# PROC054D_40MHZ_Clock.net
KiCad netlist of a schematic drawn in Altium Designer
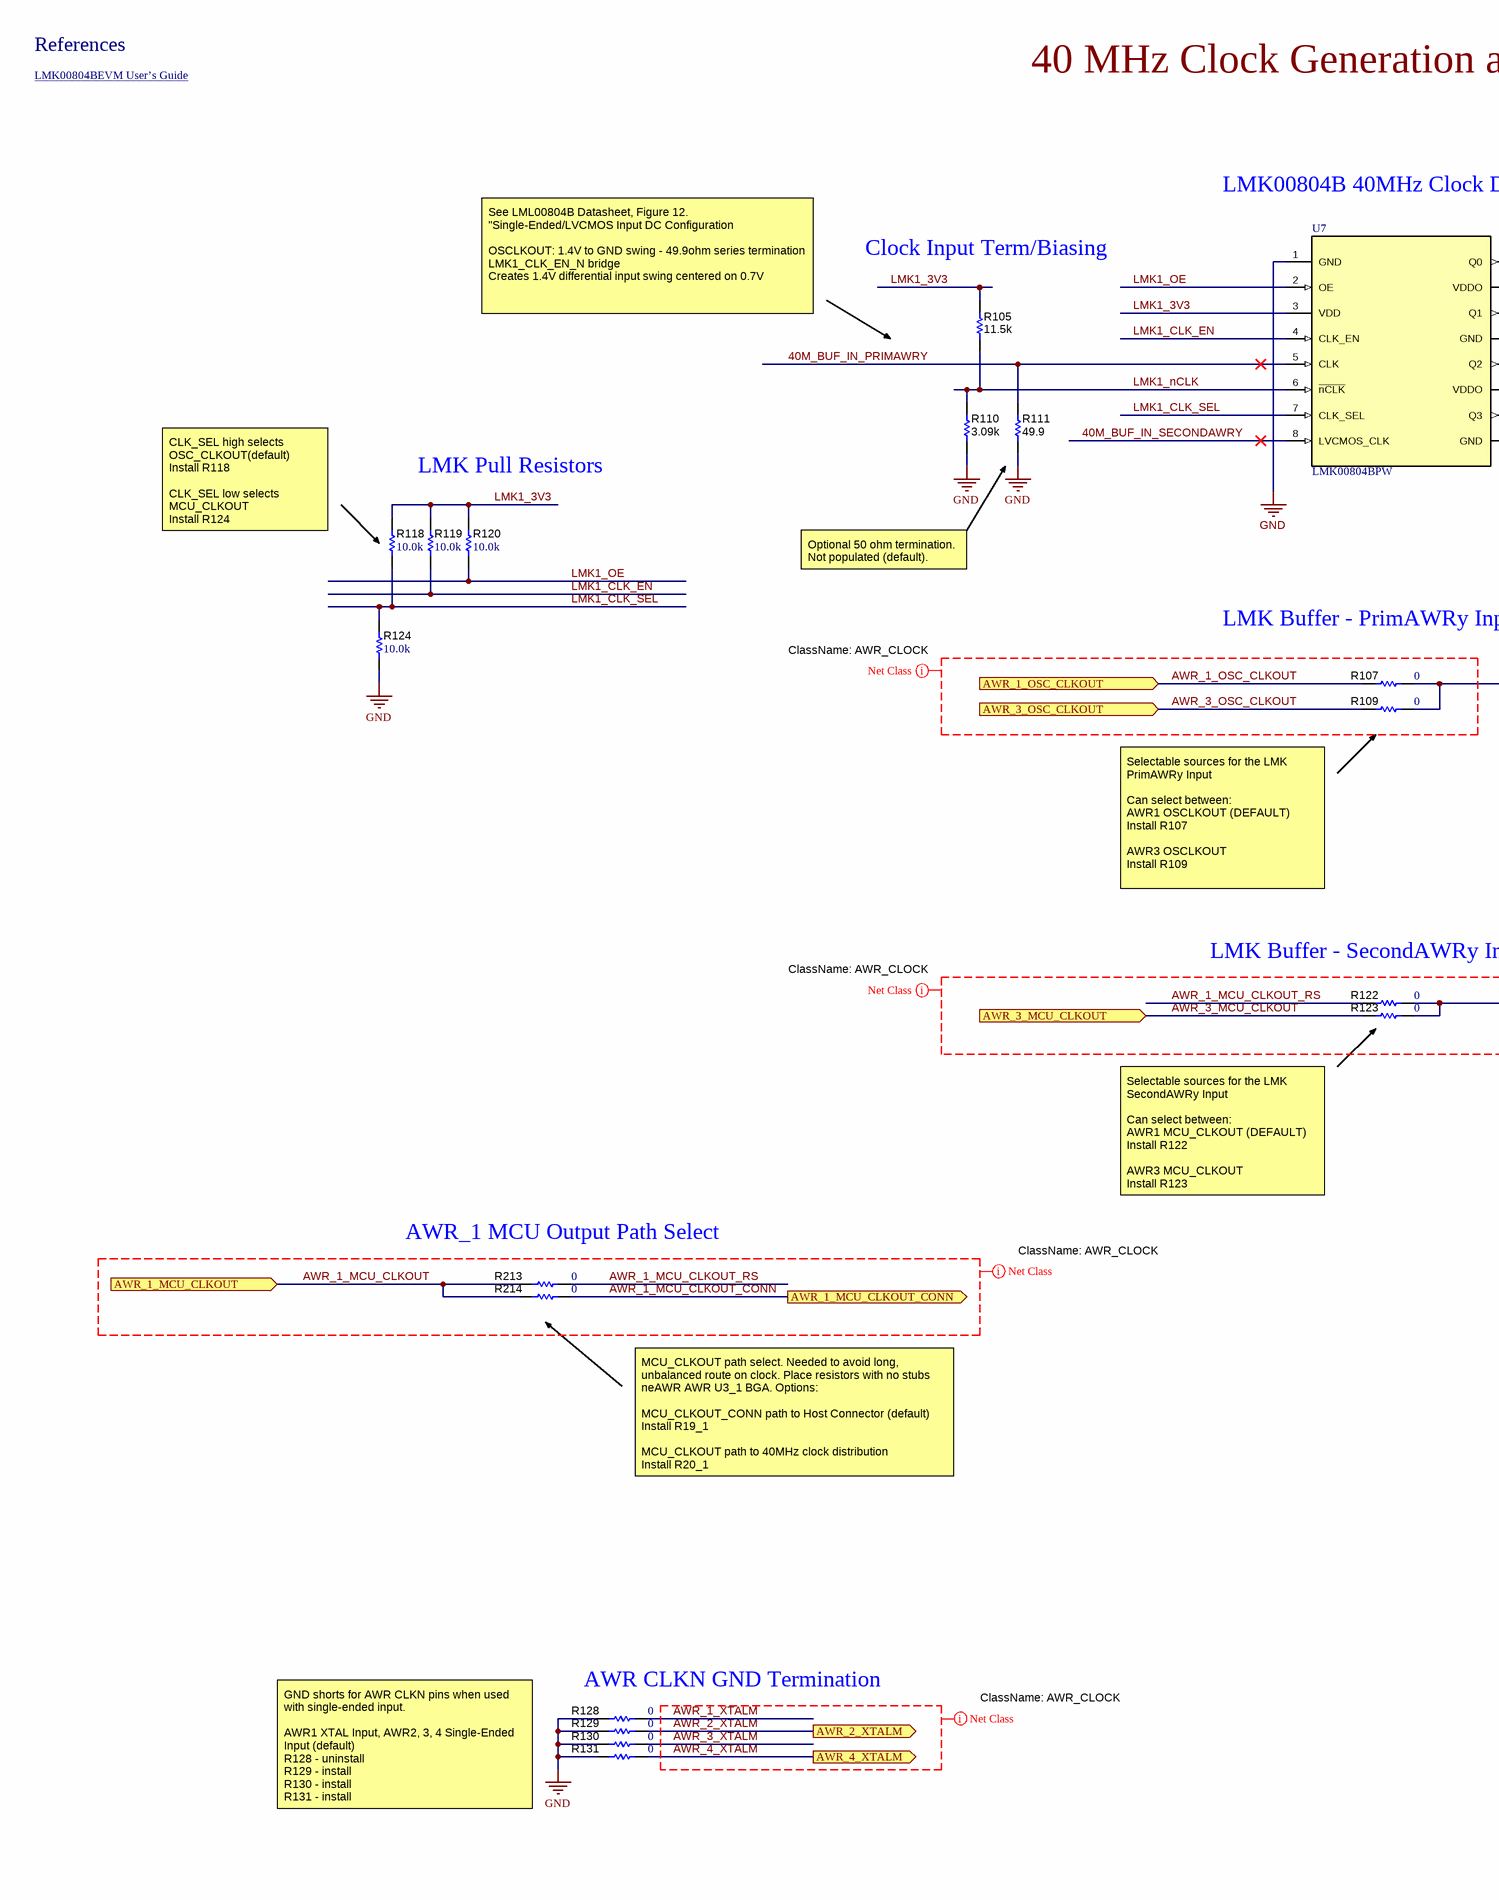
[diagram p0: PROC054D_40MHZ_Clock.SchDoc, left]
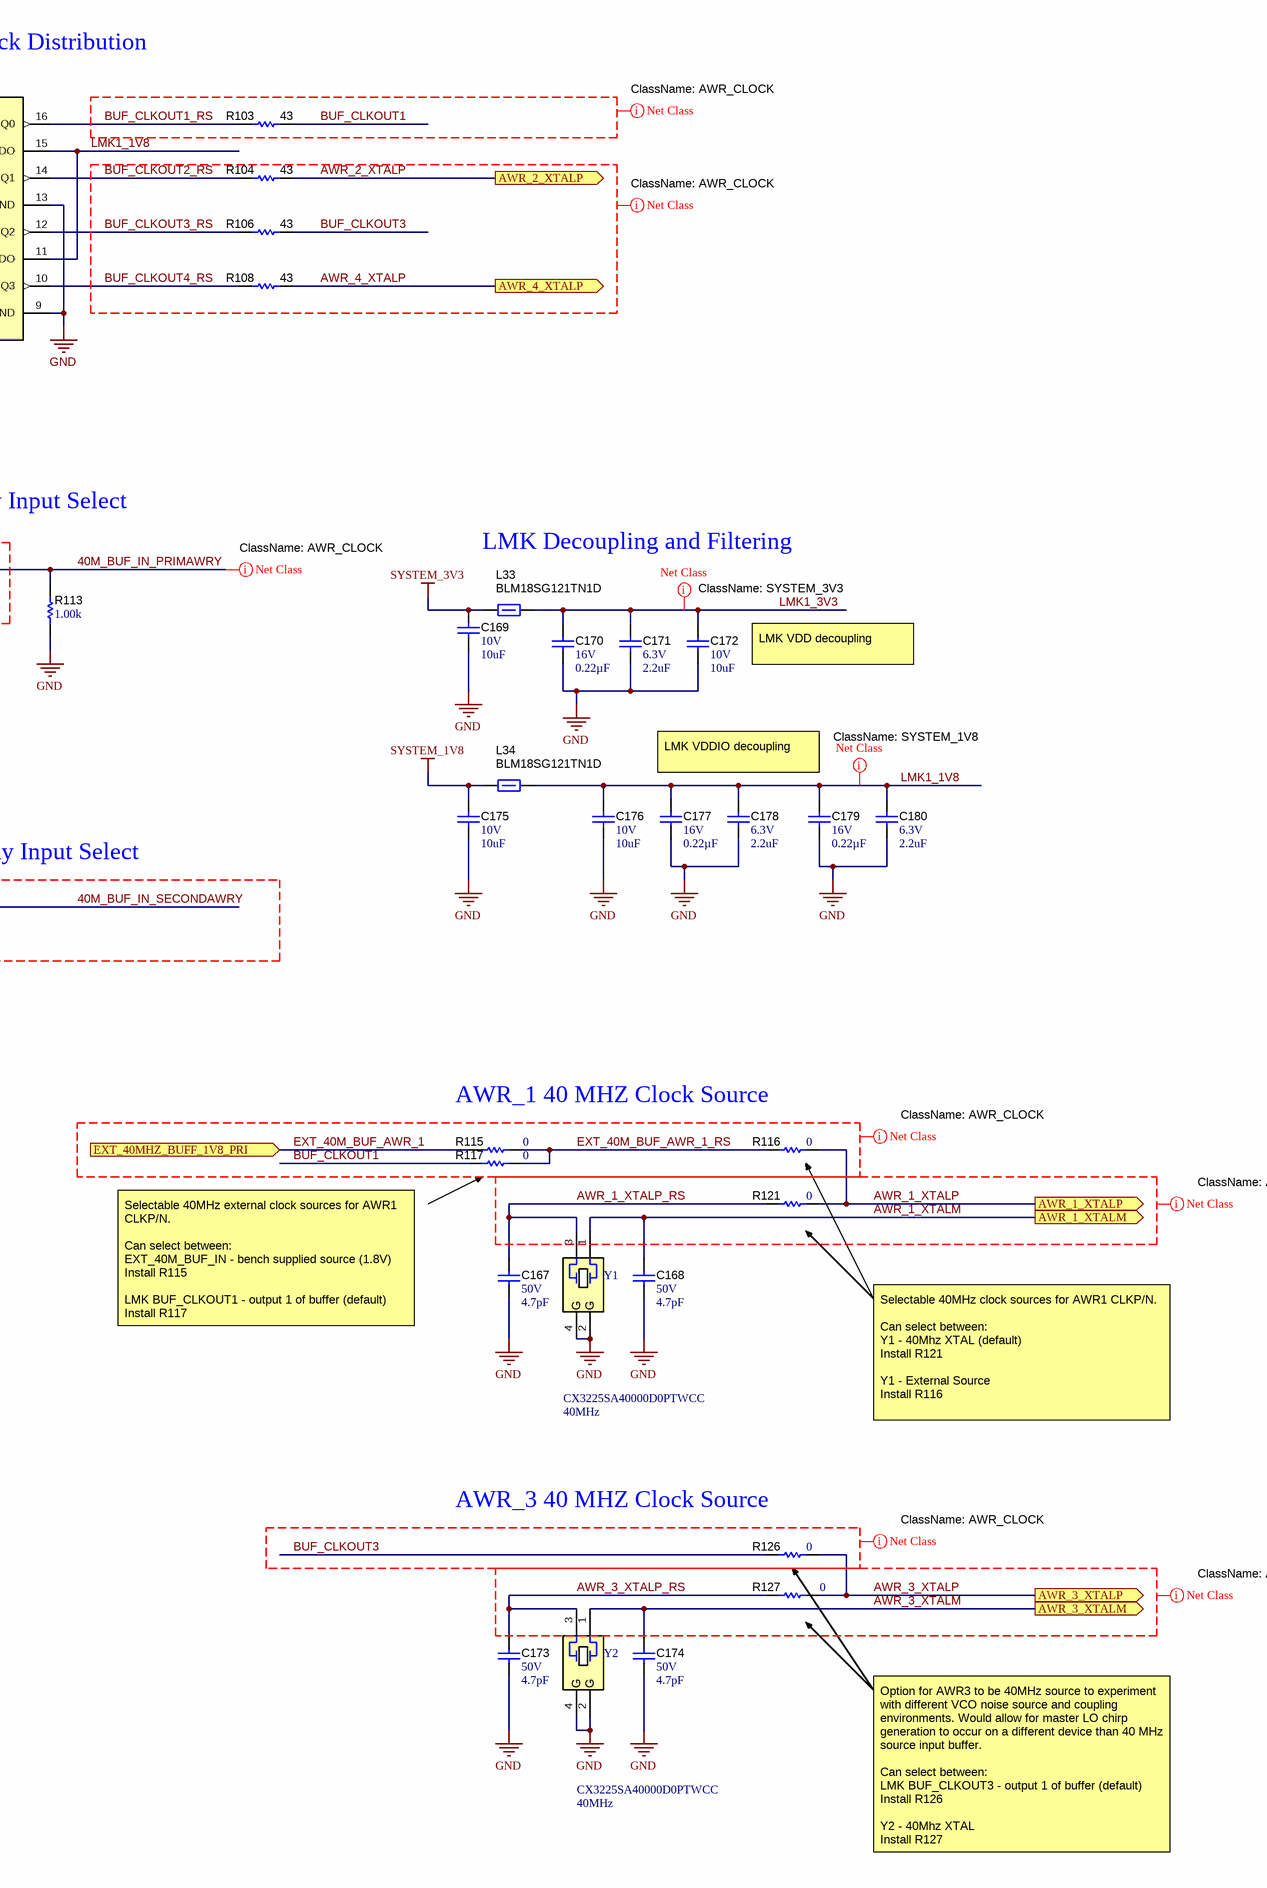
[diagram p1: PROC054D_40MHZ_Clock.SchDoc, right]

(export (version "E")
  (design (tool "Eeschema 10.0.6"))
  (components
    (comp (ref "C167")
      (value "GJM1555C1H4R7BB01D")
      (footprint "0402")
      (description "CAP, CERM, 4.7 pF, 50 V, +/- 2%, C0G/NP0, 0402")
      (fields
        (field (name "MANUFACTURER") "MuRata")
        (field (name "VDC_V") "50V")
        (field (name "VALUEDISPLAYED") "4.7pF")
        (field (name "PUBLISHER") "Texas Instruments")
      )
      (libsource (lib "Altium Vault - TI") (part "Capacitor"))
    )
    (comp (ref "C168")
      (value "GJM1555C1H4R7BB01D")
      (footprint "0402")
      (description "CAP, CERM, 4.7 pF, 50 V, +/- 2%, C0G/NP0, 0402")
      (fields
        (field (name "MANUFACTURER") "MuRata")
        (field (name "VDC_V") "50V")
        (field (name "VALUEDISPLAYED") "4.7pF")
        (field (name "PUBLISHER") "Texas Instruments")
      )
      (libsource (lib "Altium Vault - TI") (part "Capacitor"))
    )
    (comp (ref "C169")
      (value "GCM21BR71A106KE22L")
      (footprint "0805_HV")
      (description "CAP, CERM, 10 uF, 10 V, +/- 10%, X7R, 0805")
      (fields
        (field (name "MANUFACTURER") "MuRata")
        (field (name "VDC_V") "10V")
        (field (name "VALUEDISPLAYED") "10uF")
        (field (name "PUBLISHER") "Texas Instruments")
      )
      (libsource (lib "Altium Vault - TI") (part "CMP-0008017-2"))
    )
    (comp (ref "C170")
      (value "GCM155R71C224KE02D")
      (footprint "0402")
      (description "CAP, CERM, 0.22 µF, 16 V,+/- 10%, X7R, AEC-Q200 Grade 1, 0402")
      (fields
        (field (name "MANUFACTURER") "MuRata")
        (field (name "VDC_V") "16V")
        (field (name "VALUEDISPLAYED") "0.22µF")
      )
      (libsource (lib "Altium Vault - TI") (part "CMP-0078265-1"))
    )
    (comp (ref "C171")
      (value "GCM188R70J225KE22D")
      (footprint "0603")
      (description "CAP, CERM, 2.2 uF, 6.3 V, +/- 10%, X7R, AEC-Q200 Grade 1, 0603")
      (fields
        (field (name "MANUFACTURER") "MuRata")
        (field (name "VDC_V") "6.3V")
        (field (name "VALUEDISPLAYED") "2.2uF")
        (field (name "PUBLISHER") "Texas Instruments")
      )
      (libsource (lib "Altium Vault - TI") (part "Capacitor"))
    )
    (comp (ref "C172")
      (value "GCM21BR71A106KE22L")
      (footprint "0805_HV")
      (description "CAP, CERM, 10 uF, 10 V, +/- 10%, X7R, 0805")
      (fields
        (field (name "MANUFACTURER") "MuRata")
        (field (name "VDC_V") "10V")
        (field (name "VALUEDISPLAYED") "10uF")
        (field (name "PUBLISHER") "Texas Instruments")
      )
      (libsource (lib "Altium Vault - TI") (part "CMP-0008017-2"))
    )
    (comp (ref "C173")
      (value "GJM1555C1H4R7BB01D")
      (footprint "0402")
      (description "CAP, CERM, 4.7 pF, 50 V, +/- 2%, C0G/NP0, 0402")
      (fields
        (field (name "MANUFACTURER") "MuRata")
        (field (name "VDC_V") "50V")
        (field (name "VALUEDISPLAYED") "4.7pF")
        (field (name "PUBLISHER") "Texas Instruments")
      )
      (libsource (lib "Altium Vault - TI") (part "Capacitor"))
    )
    (comp (ref "C174")
      (value "GJM1555C1H4R7BB01D")
      (footprint "0402")
      (description "CAP, CERM, 4.7 pF, 50 V, +/- 2%, C0G/NP0, 0402")
      (fields
        (field (name "MANUFACTURER") "MuRata")
        (field (name "VDC_V") "50V")
        (field (name "VALUEDISPLAYED") "4.7pF")
        (field (name "PUBLISHER") "Texas Instruments")
      )
      (libsource (lib "Altium Vault - TI") (part "Capacitor"))
    )
    (comp (ref "C175")
      (value "GCM21BR71A106KE22L")
      (footprint "0805_HV")
      (description "CAP, CERM, 10 uF, 10 V, +/- 10%, X7R, 0805")
      (fields
        (field (name "MANUFACTURER") "MuRata")
        (field (name "VDC_V") "10V")
        (field (name "VALUEDISPLAYED") "10uF")
        (field (name "PUBLISHER") "Texas Instruments")
      )
      (libsource (lib "Altium Vault - TI") (part "CMP-0008017-2"))
    )
    (comp (ref "C176")
      (value "GCM21BR71A106KE22L")
      (footprint "0805_HV")
      (description "CAP, CERM, 10 uF, 10 V, +/- 10%, X7R, 0805")
      (fields
        (field (name "MANUFACTURER") "MuRata")
        (field (name "VDC_V") "10V")
        (field (name "VALUEDISPLAYED") "10uF")
        (field (name "PUBLISHER") "Texas Instruments")
      )
      (libsource (lib "Altium Vault - TI") (part "CMP-0008017-2"))
    )
    (comp (ref "C177")
      (value "GCM155R71C224KE02D")
      (footprint "0402")
      (description "CAP, CERM, 0.22 µF, 16 V,+/- 10%, X7R, AEC-Q200 Grade 1, 0402")
      (fields
        (field (name "MANUFACTURER") "MuRata")
        (field (name "VDC_V") "16V")
        (field (name "VALUEDISPLAYED") "0.22µF")
      )
      (libsource (lib "Altium Vault - TI") (part "CMP-0078265-1"))
    )
    (comp (ref "C178")
      (value "GCM188R70J225KE22D")
      (footprint "0603")
      (description "CAP, CERM, 2.2 uF, 6.3 V, +/- 10%, X7R, AEC-Q200 Grade 1, 0603")
      (fields
        (field (name "MANUFACTURER") "MuRata")
        (field (name "VDC_V") "6.3V")
        (field (name "VALUEDISPLAYED") "2.2uF")
        (field (name "PUBLISHER") "Texas Instruments")
      )
      (libsource (lib "Altium Vault - TI") (part "Capacitor"))
    )
    (comp (ref "C179")
      (value "GCM155R71C224KE02D")
      (footprint "0402")
      (description "CAP, CERM, 0.22 µF, 16 V,+/- 10%, X7R, AEC-Q200 Grade 1, 0402")
      (fields
        (field (name "MANUFACTURER") "MuRata")
        (field (name "VDC_V") "16V")
        (field (name "VALUEDISPLAYED") "0.22µF")
      )
      (libsource (lib "Altium Vault - TI") (part "CMP-0078265-1"))
    )
    (comp (ref "C180")
      (value "GCM188R70J225KE22D")
      (footprint "0603")
      (description "CAP, CERM, 2.2 uF, 6.3 V, +/- 10%, X7R, AEC-Q200 Grade 1, 0603")
      (fields
        (field (name "MANUFACTURER") "MuRata")
        (field (name "VDC_V") "6.3V")
        (field (name "VALUEDISPLAYED") "2.2uF")
        (field (name "PUBLISHER") "Texas Instruments")
      )
      (libsource (lib "Altium Vault - TI") (part "Capacitor"))
    )
    (comp (ref "L33")
      (value "BLM18SG121TN1D")
      (footprint "0603")
      (description "Ferrite Bead, 120 ohm @ 100 MHz, 3 A, 0603")
      (fields (field (name "MANUFACTURER") "MuRata") (field (name "PUBLISHER") "Texas Instruments"))
      (libsource (lib "Altium Vault - TI") (part "CMP-0003352-2"))
    )
    (comp (ref "L34")
      (value "BLM18SG121TN1D")
      (footprint "0603")
      (description "Ferrite Bead, 120 ohm @ 100 MHz, 3 A, 0603")
      (fields (field (name "MANUFACTURER") "MuRata") (field (name "PUBLISHER") "Texas Instruments"))
      (libsource (lib "Altium Vault - TI") (part "CMP-0003352-2"))
    )
    (comp (ref "R103")
      (value "CRCW040243R0JNED")
      (footprint "0402")
      (description "RES, 43, 5%, 0.063 W, AEC-Q200 Grade 0, 0402")
      (fields (field (name "MANUFACTURER") "Vishay-Dale") (field (name "VALUEDISPLAYED") "43"))
      (libsource (lib "Altium Vault - TI") (part "Resistor"))
    )
    (comp (ref "R104")
      (value "CRCW040243R0JNED")
      (footprint "0402")
      (description "RES, 43, 5%, 0.063 W, AEC-Q200 Grade 0, 0402")
      (fields (field (name "MANUFACTURER") "Vishay-Dale") (field (name "VALUEDISPLAYED") "43"))
      (libsource (lib "Altium Vault - TI") (part "Resistor"))
    )
    (comp (ref "R105")
      (value "ERJ-2RKF1152X")
      (footprint "0402")
      (description "RES, 11.5 k, 1%, 0.1 W, AEC-Q200 Grade 0, 0402")
      (fields (field (name "MANUFACTURER") "Panasonic") (field (name "VALUEDISPLAYED") "11.5k"))
      (libsource (lib "Altium Vault - TI") (part "Resistor"))
    )
    (comp (ref "R106")
      (value "CRCW040243R0JNED")
      (footprint "0402")
      (description "RES, 43, 5%, 0.063 W, AEC-Q200 Grade 0, 0402")
      (fields (field (name "MANUFACTURER") "Vishay-Dale") (field (name "VALUEDISPLAYED") "43"))
      (libsource (lib "Altium Vault - TI") (part "Resistor"))
    )
    (comp (ref "R107")
      (value "ERJ-2GE0R00X")
      (footprint "0402")
      (description "RES, 0, 5%, 0.1 W, AEC-Q200 Grade 0, 0402")
      (fields (field (name "MANUFACTURER") "Panasonic") (field (name "VALUEDISPLAYED") "0"))
      (libsource (lib "Altium Vault - TI") (part "Resistor"))
    )
    (comp (ref "R108")
      (value "CRCW040243R0JNED")
      (footprint "0402")
      (description "RES, 43, 5%, 0.063 W, AEC-Q200 Grade 0, 0402")
      (fields (field (name "MANUFACTURER") "Vishay-Dale") (field (name "VALUEDISPLAYED") "43"))
      (libsource (lib "Altium Vault - TI") (part "Resistor"))
    )
    (comp (ref "R109")
      (value "ERJ-2GE0R00X")
      (footprint "0402")
      (description "RES, 0, 5%, 0.1 W, AEC-Q200 Grade 0, 0402")
      (fields (field (name "MANUFACTURER") "Panasonic") (field (name "VALUEDISPLAYED") "0"))
      (libsource (lib "Altium Vault - TI") (part "Resistor"))
    )
    (comp (ref "R110")
      (value "ERJ-2RKF3091X")
      (footprint "0402")
      (description "RES, 3.09 k, 1%, 0.1 W, AEC-Q200 Grade 0, 0402")
      (fields (field (name "MANUFACTURER") "Panasonic") (field (name "VALUEDISPLAYED") "3.09k"))
      (libsource (lib "Altium Vault - TI") (part "Resistor"))
    )
    (comp (ref "R111")
      (value "ERJ-2RKF49R9X")
      (footprint "0402")
      (description "RES, 49.9, 1%, 0.1 W, AEC-Q200 Grade 0, 0402")
      (fields
        (field (name "MANUFACTURER") "Panasonic")
        (field (name "VALUEDISPLAYED") "49.9")
        (field (name "PUBLISHER") "Texas Instruments")
      )
      (libsource (lib "Altium Vault - TI") (part "Resistor"))
    )
    (comp (ref "R113")
      (value "CRCW04021K00FKED")
      (footprint "0402")
      (description "RES, 1.00 k, 1%, 0.063 W, AEC-Q200 Grade 0, 0402")
      (fields (field (name "MANUFACTURER") "Vishay-Dale") (field (name "VALUEDISPLAYED") "1.00k"))
      (libsource (lib "Altium Vault - TI") (part "Resistor"))
    )
    (comp (ref "R115")
      (value "ERJ-2GE0R00X")
      (footprint "0402")
      (description "RES, 0, 5%, 0.1 W, AEC-Q200 Grade 0, 0402")
      (fields (field (name "MANUFACTURER") "Panasonic") (field (name "VALUEDISPLAYED") "0"))
      (libsource (lib "Altium Vault - TI") (part "CMP-0026992-3"))
    )
    (comp (ref "R116")
      (value "ERJ-2GE0R00X")
      (footprint "0402")
      (description "RES, 0, 5%, 0.1 W, AEC-Q200 Grade 0, 0402")
      (fields (field (name "MANUFACTURER") "Panasonic") (field (name "VALUEDISPLAYED") "0"))
      (libsource (lib "Altium Vault - TI") (part "CMP-0026992-3"))
    )
    (comp (ref "R117")
      (value "ERJ-2GE0R00X")
      (footprint "0402")
      (description "RES, 0, 5%, 0.1 W, AEC-Q200 Grade 0, 0402")
      (fields (field (name "MANUFACTURER") "Panasonic") (field (name "VALUEDISPLAYED") "0"))
      (libsource (lib "Altium Vault - TI") (part "Resistor"))
    )
    (comp (ref "R118")
      (value "CRCW040210K0FKED")
      (footprint "0402")
      (description "RES, 10.0 k, 1%, 0.063 W, AEC-Q200 Grade 0, 0402")
      (fields (field (name "MANUFACTURER") "Vishay-Dale") (field (name "VALUEDISPLAYED") "10.0k"))
      (libsource (lib "Altium Vault - TI") (part "Resistor"))
    )
    (comp (ref "R119")
      (value "CRCW040210K0FKED")
      (footprint "0402")
      (description "RES, 10.0 k, 1%, 0.063 W, AEC-Q200 Grade 0, 0402")
      (fields (field (name "MANUFACTURER") "Vishay-Dale") (field (name "VALUEDISPLAYED") "10.0k"))
      (libsource (lib "Altium Vault - TI") (part "Resistor"))
    )
    (comp (ref "R120")
      (value "CRCW040210K0FKED")
      (footprint "0402")
      (description "RES, 10.0 k, 1%, 0.063 W, AEC-Q200 Grade 0, 0402")
      (fields (field (name "MANUFACTURER") "Vishay-Dale") (field (name "VALUEDISPLAYED") "10.0k"))
      (libsource (lib "Altium Vault - TI") (part "Resistor"))
    )
    (comp (ref "R121")
      (value "ERJ-2GE0R00X")
      (footprint "0402")
      (description "RES, 0, 5%, 0.1 W, AEC-Q200 Grade 0, 0402")
      (fields (field (name "MANUFACTURER") "Panasonic") (field (name "VALUEDISPLAYED") "0"))
      (libsource (lib "Altium Vault - TI") (part "CMP-0026992-3"))
    )
    (comp (ref "R122")
      (value "ERJ-2GE0R00X")
      (footprint "0402")
      (description "RES, 0, 5%, 0.1 W, AEC-Q200 Grade 0, 0402")
      (fields (field (name "MANUFACTURER") "Panasonic") (field (name "VALUEDISPLAYED") "0"))
      (libsource (lib "Altium Vault - TI") (part "Resistor"))
    )
    (comp (ref "R123")
      (value "ERJ-2GE0R00X")
      (footprint "0402")
      (description "RES, 0, 5%, 0.1 W, AEC-Q200 Grade 0, 0402")
      (fields (field (name "MANUFACTURER") "Panasonic") (field (name "VALUEDISPLAYED") "0"))
      (libsource (lib "Altium Vault - TI") (part "Resistor"))
    )
    (comp (ref "R124")
      (value "CRCW040210K0FKED")
      (footprint "0402")
      (description "RES, 10.0 k, 1%, 0.063 W, AEC-Q200 Grade 0, 0402")
      (fields (field (name "MANUFACTURER") "Vishay-Dale") (field (name "VALUEDISPLAYED") "10.0k"))
      (libsource (lib "Altium Vault - TI") (part "Resistor"))
    )
    (comp (ref "R126")
      (value "ERJ-2GE0R00X")
      (footprint "0402")
      (description "RES, 0, 5%, 0.1 W, AEC-Q200 Grade 0, 0402")
      (fields (field (name "MANUFACTURER") "Panasonic") (field (name "VALUEDISPLAYED") "0"))
      (libsource (lib "Altium Vault - TI") (part "CMP-0026992-3"))
    )
    (comp (ref "R127")
      (value "CRCW02010000Z0ED")
      (footprint "0201")
      (description "RES, 0, 5%, 0.05 W, 0201")
      (fields (field (name "MANUFACTURER") "Vishay-Dale") (field (name "VALUEDISPLAYED") "0"))
      (libsource (lib "Altium Vault - TI") (part "Resistor"))
    )
    (comp (ref "R128")
      (value "ERJ-2GE0R00X")
      (footprint "0402")
      (description "RES, 0, 5%, 0.1 W, AEC-Q200 Grade 0, 0402")
      (fields (field (name "MANUFACTURER") "Panasonic") (field (name "VALUEDISPLAYED") "0"))
      (libsource (lib "Altium Vault - TI") (part "CMP-0026992-3"))
    )
    (comp (ref "R129")
      (value "ERJ-2GE0R00X")
      (footprint "0402")
      (description "RES, 0, 5%, 0.1 W, AEC-Q200 Grade 0, 0402")
      (fields (field (name "MANUFACTURER") "Panasonic") (field (name "VALUEDISPLAYED") "0"))
      (libsource (lib "Altium Vault - TI") (part "Resistor"))
    )
    (comp (ref "R130")
      (value "ERJ-2GE0R00X")
      (footprint "0402")
      (description "RES, 0, 5%, 0.1 W, AEC-Q200 Grade 0, 0402")
      (fields (field (name "MANUFACTURER") "Panasonic") (field (name "VALUEDISPLAYED") "0"))
      (libsource (lib "Altium Vault - TI") (part "Resistor"))
    )
    (comp (ref "R131")
      (value "ERJ-2GE0R00X")
      (footprint "0402")
      (description "RES, 0, 5%, 0.1 W, AEC-Q200 Grade 0, 0402")
      (fields (field (name "MANUFACTURER") "Panasonic") (field (name "VALUEDISPLAYED") "0"))
      (libsource (lib "Altium Vault - TI") (part "Resistor"))
    )
    (comp (ref "R213")
      (value "ERJ-2GE0R00X")
      (footprint "0402S")
      (description "RES, 0, 5%, 0.1 W, AEC-Q200 Grade 0, 0402")
      (fields (field (name "MANUFACTURER") "Panasonic") (field (name "VALUEDISPLAYED") "0"))
      (libsource (lib "Altium Vault - TI") (part "Resistor"))
    )
    (comp (ref "R214")
      (value "ERJ-2GE0R00X")
      (footprint "0402S")
      (description "RES, 0, 5%, 0.1 W, AEC-Q200 Grade 0, 0402")
      (fields (field (name "MANUFACTURER") "Panasonic") (field (name "VALUEDISPLAYED") "0"))
      (libsource (lib "Altium Vault - TI") (part "Resistor"))
    )
    (comp (ref "U7")
      (value "LMK00804BPW")
      (footprint "PW0016A_N")
      (description "Low Skew, 1-to-4 Multiplexed Differential/LVCMOS-to-LVCMOS/TTL Fanout Buffer, PW0016A (TSSOP-16)")
      (fields
        (field (name "MANUFACTURER") "Texas Instruments")
        (field (name "PARTNUMBER") "LMK00804BPW")
        (field (name "PUBLISHER") "Texas Instruments")
      )
      (libsource (lib "Altium Vault - TI") (part "CMP-0065663-1"))
    )
    (comp (ref "Y1")
      (value "CX3225SA40000D0PTWCC")
      (footprint "Kyocera_CX3225SA")
      (description "Crystal, 40 MHz, 8pF, SMD")
      (fields
        (field (name "FREQUENCY_FIXED") "40MHz")
        (field (name "MANUFACTURER") "Kyocera")
        (field (name "PARTNUMBER") "CX3225SA40000D0PTWCC")
      )
      (libsource (lib "Altium Vault - TI") (part "CMP-0004694-3"))
    )
    (comp (ref "Y2")
      (value "CX3225SA40000D0PTWCC")
      (footprint "Kyocera_CX3225SA")
      (description "Crystal, 40 MHz, 8pF, SMD")
      (fields
        (field (name "FREQUENCY_FIXED") "40MHz")
        (field (name "MANUFACTURER") "Kyocera")
        (field (name "PARTNUMBER") "CX3225SA40000D0PTWCC")
      )
      (libsource (lib "Altium Vault - TI") (part "CMP-0004694-3"))
    )
  )
  (nets
    (net (code "1") (name "/40M_BUF_IN_PRIMAWRY") (class "Default")
      (node (ref "R107") (pin "2") (pinfunction "2_2") (pintype "passive"))
      (node (ref "R109") (pin "2") (pinfunction "2_2") (pintype "passive"))
      (node (ref "R111") (pin "2") (pinfunction "2_2") (pintype "passive"))
      (node (ref "R113") (pin "2") (pinfunction "2_2") (pintype "passive"))
      (node (ref "U7") (pin "5") (pinfunction "CLK_5") (pintype "input"))
    )
    (net (code "2") (name "/40M_BUF_IN_SECONDAWRY") (class "Default")
      (node (ref "R122") (pin "2") (pinfunction "2_2") (pintype "passive"))
      (node (ref "R123") (pin "2") (pinfunction "2_2") (pintype "passive"))
      (node (ref "U7") (pin "8") (pinfunction "LVCMOS_CLK_8") (pintype "input"))
    )
    (net (code "3") (name "/AWR_1_MCU_CLKOUT") (class "Default")
      (node (ref "R213") (pin "1") (pinfunction "1_1") (pintype "passive"))
      (node (ref "R214") (pin "1") (pinfunction "1_1") (pintype "passive"))
    )
    (net (code "4") (name "/AWR_1_MCU_CLKOUT_CONN") (class "Default")
      (node (ref "R214") (pin "2") (pinfunction "2_2") (pintype "passive"))
    )
    (net (code "5") (name "/AWR_1_MCU_CLKOUT_RS") (class "Default")
      (node (ref "R122") (pin "1") (pinfunction "1_1") (pintype "passive"))
      (node (ref "R213") (pin "2") (pinfunction "2_2") (pintype "passive"))
    )
    (net (code "6") (name "/AWR_1_OSC_CLKOUT") (class "Default")
      (node (ref "R107") (pin "1") (pinfunction "1_1") (pintype "passive"))
    )
    (net (code "7") (name "/AWR_1_XTALM") (class "Default")
      (node (ref "C168") (pin "2") (pinfunction "2_2") (pintype "passive"))
      (node (ref "R128") (pin "1") (pinfunction "1_1") (pintype "passive"))
      (node (ref "Y1") (pin "1") (pinfunction "1_1") (pintype "passive"))
    )
    (net (code "8") (name "/AWR_1_XTALP") (class "Default")
      (node (ref "R116") (pin "2") (pinfunction "2_2") (pintype "passive"))
      (node (ref "R121") (pin "2") (pinfunction "2_2") (pintype "passive"))
    )
    (net (code "9") (name "/AWR_1_XTALP_RS") (class "Default")
      (node (ref "C167") (pin "1") (pinfunction "1_1") (pintype "passive"))
      (node (ref "R121") (pin "1") (pinfunction "1_1") (pintype "passive"))
      (node (ref "Y1") (pin "3") (pinfunction "3_3") (pintype "passive"))
    )
    (net (code "10") (name "/AWR_2_XTALM") (class "Default")
      (node (ref "R129") (pin "2") (pinfunction "2_2") (pintype "passive"))
    )
    (net (code "11") (name "/AWR_2_XTALP") (class "Default")
      (node (ref "R104") (pin "2") (pinfunction "2_2") (pintype "passive"))
    )
    (net (code "12") (name "/AWR_3_MCU_CLKOUT") (class "Default")
      (node (ref "R123") (pin "1") (pinfunction "1_1") (pintype "passive"))
    )
    (net (code "13") (name "/AWR_3_OSC_CLKOUT") (class "Default")
      (node (ref "R109") (pin "1") (pinfunction "1_1") (pintype "passive"))
    )
    (net (code "14") (name "/AWR_3_XTALM") (class "Default")
      (node (ref "C174") (pin "1") (pinfunction "1_1") (pintype "passive"))
      (node (ref "R130") (pin "2") (pinfunction "2_2") (pintype "passive"))
      (node (ref "Y2") (pin "1") (pinfunction "1_1") (pintype "passive"))
    )
    (net (code "15") (name "/AWR_3_XTALP") (class "Default")
      (node (ref "R126") (pin "2") (pinfunction "2_2") (pintype "passive"))
      (node (ref "R127") (pin "2") (pinfunction "2_2") (pintype "passive"))
    )
    (net (code "16") (name "/AWR_3_XTALP_RS") (class "Default")
      (node (ref "C173") (pin "1") (pinfunction "1_1") (pintype "passive"))
      (node (ref "R127") (pin "1") (pinfunction "1_1") (pintype "passive"))
      (node (ref "Y2") (pin "3") (pinfunction "3_3") (pintype "passive"))
    )
    (net (code "17") (name "/AWR_4_XTALM") (class "Default")
      (node (ref "R131") (pin "2") (pinfunction "2_2") (pintype "passive"))
    )
    (net (code "18") (name "/AWR_4_XTALP") (class "Default")
      (node (ref "R108") (pin "2") (pinfunction "2_2") (pintype "passive"))
    )
    (net (code "19") (name "/BUF_CLKOUT1") (class "Default")
      (node (ref "R103") (pin "2") (pinfunction "2_2") (pintype "passive"))
      (node (ref "R117") (pin "1") (pinfunction "1_1") (pintype "passive"))
    )
    (net (code "20") (name "/BUF_CLKOUT1_RS") (class "Default")
      (node (ref "R103") (pin "1") (pinfunction "1_1") (pintype "passive"))
      (node (ref "U7") (pin "16") (pinfunction "Q0_16") (pintype "output"))
    )
    (net (code "21") (name "/BUF_CLKOUT2_RS") (class "Default")
      (node (ref "R104") (pin "1") (pinfunction "1_1") (pintype "passive"))
      (node (ref "U7") (pin "14") (pinfunction "Q1_14") (pintype "output"))
    )
    (net (code "22") (name "/BUF_CLKOUT3") (class "Default")
      (node (ref "R106") (pin "2") (pinfunction "2_2") (pintype "passive"))
      (node (ref "R126") (pin "1") (pinfunction "1_1") (pintype "passive"))
    )
    (net (code "23") (name "/BUF_CLKOUT3_RS") (class "Default")
      (node (ref "R106") (pin "1") (pinfunction "1_1") (pintype "passive"))
      (node (ref "U7") (pin "12") (pinfunction "Q2_12") (pintype "output"))
    )
    (net (code "24") (name "/BUF_CLKOUT4_RS") (class "Default")
      (node (ref "R108") (pin "1") (pinfunction "1_1") (pintype "passive"))
      (node (ref "U7") (pin "10") (pinfunction "Q3_10") (pintype "output"))
    )
    (net (code "25") (name "/EXT_40M_BUF_AWR_1") (class "Default")
      (node (ref "R115") (pin "1") (pinfunction "1_1") (pintype "passive"))
    )
    (net (code "26") (name "/EXT_40M_BUF_AWR_1_RS") (class "Default")
      (node (ref "R115") (pin "2") (pinfunction "2_2") (pintype "passive"))
      (node (ref "R116") (pin "1") (pinfunction "1_1") (pintype "passive"))
      (node (ref "R117") (pin "2") (pinfunction "2_2") (pintype "passive"))
    )
    (net (code "27") (name "/LMK1_1V8") (class "Default")
      (node (ref "C176") (pin "1") (pinfunction "1_1") (pintype "passive"))
      (node (ref "C177") (pin "1") (pinfunction "1_1") (pintype "passive"))
      (node (ref "C178") (pin "2") (pinfunction "2_2") (pintype "passive"))
      (node (ref "C179") (pin "1") (pinfunction "1_1") (pintype "passive"))
      (node (ref "C180") (pin "2") (pinfunction "2_2") (pintype "passive"))
      (node (ref "L34") (pin "2") (pinfunction "2_2") (pintype "passive"))
      (node (ref "U7") (pin "11") (pinfunction "VDDO_11") (pintype "power_in"))
      (node (ref "U7") (pin "15") (pinfunction "VDDO_15") (pintype "power_in"))
    )
    (net (code "28") (name "/LMK1_3V3") (class "Default")
      (node (ref "C170") (pin "1") (pinfunction "1_1") (pintype "passive"))
      (node (ref "C171") (pin "2") (pinfunction "2_2") (pintype "passive"))
      (node (ref "C172") (pin "1") (pinfunction "1_1") (pintype "passive"))
      (node (ref "L33") (pin "2") (pinfunction "2_2") (pintype "passive"))
      (node (ref "R105") (pin "2") (pinfunction "2_2") (pintype "passive"))
      (node (ref "R118") (pin "2") (pinfunction "2_2") (pintype "passive"))
      (node (ref "R119") (pin "2") (pinfunction "2_2") (pintype "passive"))
      (node (ref "R120") (pin "2") (pinfunction "2_2") (pintype "passive"))
      (node (ref "U7") (pin "3") (pinfunction "VDD_3") (pintype "power_in"))
    )
    (net (code "29") (name "/LMK1_CLK_EN") (class "Default")
      (node (ref "R119") (pin "1") (pinfunction "1_1") (pintype "passive"))
      (node (ref "U7") (pin "4") (pinfunction "CLK_EN_4") (pintype "input"))
    )
    (net (code "30") (name "/LMK1_CLK_SEL") (class "Default")
      (node (ref "R118") (pin "1") (pinfunction "1_1") (pintype "passive"))
      (node (ref "R124") (pin "2") (pinfunction "2_2") (pintype "passive"))
      (node (ref "U7") (pin "7") (pinfunction "CLK_SEL_7") (pintype "input"))
    )
    (net (code "31") (name "/LMK1_OE") (class "Default")
      (node (ref "R120") (pin "1") (pinfunction "1_1") (pintype "passive"))
      (node (ref "U7") (pin "2") (pinfunction "OE_2") (pintype "input"))
    )
    (net (code "32") (name "/LMK1_nCLK") (class "Default")
      (node (ref "R105") (pin "1") (pinfunction "1_1") (pintype "passive"))
      (node (ref "R110") (pin "2") (pinfunction "2_2") (pintype "passive"))
      (node (ref "U7") (pin "6") (pinfunction "nCLK_6") (pintype "input"))
    )
    (net (code "33") (name "GND") (class "Default")
      (node (ref "C167") (pin "2") (pinfunction "2_2") (pintype "passive"))
      (node (ref "C168") (pin "1") (pinfunction "1_1") (pintype "passive"))
      (node (ref "C169") (pin "2") (pinfunction "2_2") (pintype "passive"))
      (node (ref "C170") (pin "2") (pinfunction "2_2") (pintype "passive"))
      (node (ref "C171") (pin "1") (pinfunction "1_1") (pintype "passive"))
      (node (ref "C172") (pin "2") (pinfunction "2_2") (pintype "passive"))
      (node (ref "C173") (pin "2") (pinfunction "2_2") (pintype "passive"))
      (node (ref "C174") (pin "2") (pinfunction "2_2") (pintype "passive"))
      (node (ref "C175") (pin "2") (pinfunction "2_2") (pintype "passive"))
      (node (ref "C176") (pin "2") (pinfunction "2_2") (pintype "passive"))
      (node (ref "C177") (pin "2") (pinfunction "2_2") (pintype "passive"))
      (node (ref "C178") (pin "1") (pinfunction "1_1") (pintype "passive"))
      (node (ref "C179") (pin "2") (pinfunction "2_2") (pintype "passive"))
      (node (ref "C180") (pin "1") (pinfunction "1_1") (pintype "passive"))
      (node (ref "R110") (pin "1") (pinfunction "1_1") (pintype "passive"))
      (node (ref "R111") (pin "1") (pinfunction "1_1") (pintype "passive"))
      (node (ref "R113") (pin "1") (pinfunction "1_1") (pintype "passive"))
      (node (ref "R124") (pin "1") (pinfunction "1_1") (pintype "passive"))
      (node (ref "R128") (pin "2") (pinfunction "2_2") (pintype "passive"))
      (node (ref "R129") (pin "1") (pinfunction "1_1") (pintype "passive"))
      (node (ref "R130") (pin "1") (pinfunction "1_1") (pintype "passive"))
      (node (ref "R131") (pin "1") (pinfunction "1_1") (pintype "passive"))
      (node (ref "U7") (pin "1") (pinfunction "GND_1") (pintype "power_in"))
      (node (ref "U7") (pin "13") (pinfunction "GND_13") (pintype "power_in"))
      (node (ref "U7") (pin "9") (pinfunction "GND_9") (pintype "power_in"))
      (node (ref "Y1") (pin "2") (pinfunction "GND_2") (pintype "power_in"))
      (node (ref "Y1") (pin "4") (pinfunction "GND_4") (pintype "power_in"))
      (node (ref "Y2") (pin "2") (pinfunction "GND_2") (pintype "power_in"))
      (node (ref "Y2") (pin "4") (pinfunction "GND_4") (pintype "power_in"))
    )
    (net (code "34") (name "SYSTEM_1V8") (class "Default")
      (node (ref "C175") (pin "1") (pinfunction "1_1") (pintype "passive"))
      (node (ref "L34") (pin "1") (pinfunction "1_1") (pintype "passive"))
    )
    (net (code "35") (name "SYSTEM_3V3") (class "Default")
      (node (ref "C169") (pin "1") (pinfunction "1_1") (pintype "passive"))
      (node (ref "L33") (pin "1") (pinfunction "1_1") (pintype "passive"))
    )
  )
)
